# Xadow_-_GSM_Breakout_v1_0.net
KiCad netlist of a schematic drawn in EAGLE
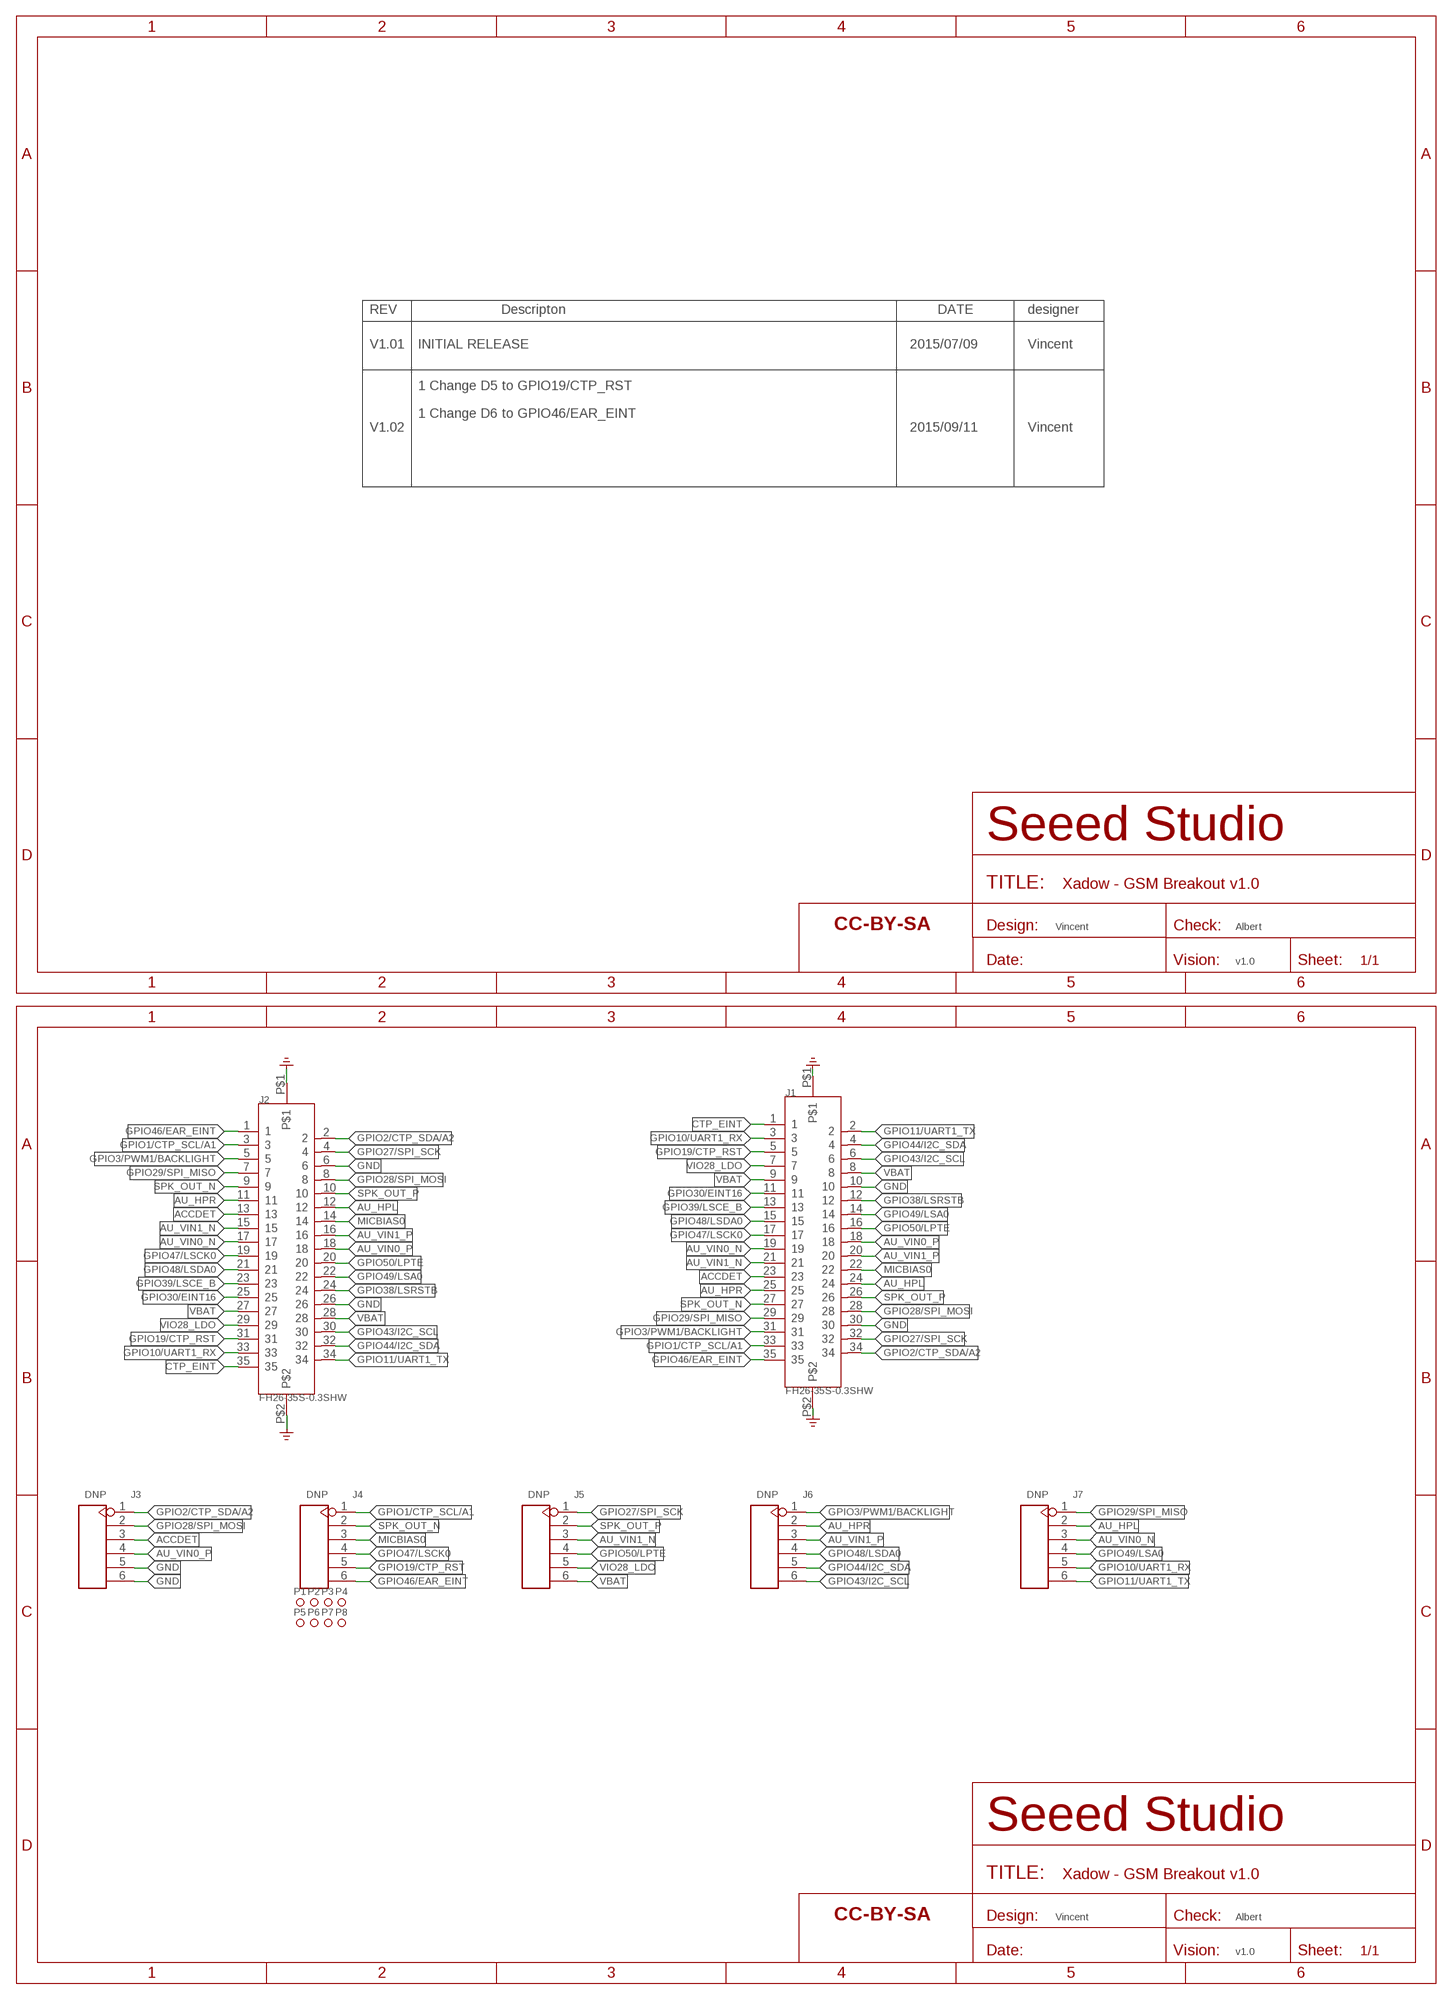
[diagram p0: schematic, sheet 1]

(export (version "E")
  (design (tool "Eeschema 10.0.6"))
  (components
    (comp (ref "FR1")
      (value "SEEEDSTUDIO-OPEN-SCH-FRAME")
      (footprint "eagle-import:SEEEDSTUDIO-PCB-FRAME")
      (libsource (lib "eagle-import") (part "SEEEDSTUDIO-OPEN-SCH-FRAME"))
    )
    (comp (ref "FR2")
      (value "SEEEDSTUDIO-OPEN-SCH-FRAME")
      (footprint "eagle-import:SEEEDSTUDIO-PCB-FRAME")
      (libsource (lib "eagle-import") (part "SEEEDSTUDIO-OPEN-SCH-FRAME"))
    )
    (comp (ref "J1")
      (value "FH26-35S-0.3SHW")
      (footprint "eagle-import:FPC35-SMD-0.3(FH26W)")
      (libsource (lib "eagle-import") (part "FPC-CONNECTER-35P(FH26W-35S-0.3SHW(10))"))
    )
    (comp (ref "J2")
      (value "FH26-35S-0.3SHW")
      (footprint "eagle-import:FPC35-SMD-0.3(FH26W)")
      (libsource (lib "eagle-import") (part "FPC-CONNECTER-35P(FH26W-35S-0.3SHW(10))"))
    )
    (comp (ref "J3")
      (value "DNP")
      (footprint "eagle-import:H6-2.54-C65D35MIL")
      (libsource (lib "eagle-import") (part "HEADER-6P-65/35MIL"))
    )
    (comp (ref "J4")
      (value "DNP")
      (footprint "eagle-import:H6-2.54-C65D35MIL")
      (libsource (lib "eagle-import") (part "HEADER-6P-65/35MIL"))
    )
    (comp (ref "J5")
      (value "DNP")
      (footprint "eagle-import:H6-2.54-C65D35MIL")
      (libsource (lib "eagle-import") (part "HEADER-6P-65/35MIL"))
    )
    (comp (ref "J6")
      (value "DNP")
      (footprint "eagle-import:H6-2.54-C65D35MIL")
      (libsource (lib "eagle-import") (part "HEADER-6P-65/35MIL"))
    )
    (comp (ref "J7")
      (value "DNP")
      (footprint "eagle-import:H6-2.54-C65D35MIL")
      (libsource (lib "eagle-import") (part "HEADER-6P-65/35MIL"))
    )
    (comp (ref "P1")
      (value "MARK-1.0'ANNULAR'")
      (footprint "eagle-import:ROUND-MARK-1.0")
      (fields (field (name "PARTNO") "DNP"))
      (libsource (lib "eagle-import") (part "MARK-1.0'ANNULAR'"))
    )
    (comp (ref "P2")
      (value "MARK-1.0'ANNULAR'")
      (footprint "eagle-import:ROUND-MARK-1.0")
      (fields (field (name "PARTNO") "DNP"))
      (libsource (lib "eagle-import") (part "MARK-1.0'ANNULAR'"))
    )
    (comp (ref "P3")
      (value "MARK-1.0'ANNULAR'")
      (footprint "eagle-import:ROUND-MARK-1.0")
      (fields (field (name "PARTNO") "DNP"))
      (libsource (lib "eagle-import") (part "MARK-1.0'ANNULAR'"))
    )
    (comp (ref "P4")
      (value "MARK-1.0'ANNULAR'")
      (footprint "eagle-import:ROUND-MARK-1.0")
      (fields (field (name "PARTNO") "DNP"))
      (libsource (lib "eagle-import") (part "MARK-1.0'ANNULAR'"))
    )
    (comp (ref "P5")
      (value "MARK-1.0'ANNULAR'")
      (footprint "eagle-import:ROUND-MARK-1.0")
      (fields (field (name "PARTNO") "DNP"))
      (libsource (lib "eagle-import") (part "MARK-1.0'ANNULAR'"))
    )
    (comp (ref "P6")
      (value "MARK-1.0'ANNULAR'")
      (footprint "eagle-import:ROUND-MARK-1.0")
      (fields (field (name "PARTNO") "DNP"))
      (libsource (lib "eagle-import") (part "MARK-1.0'ANNULAR'"))
    )
    (comp (ref "P7")
      (value "MARK-1.0'ANNULAR'")
      (footprint "eagle-import:ROUND-MARK-1.0")
      (fields (field (name "PARTNO") "DNP"))
      (libsource (lib "eagle-import") (part "MARK-1.0'ANNULAR'"))
    )
    (comp (ref "P8")
      (value "MARK-1.0'ANNULAR'")
      (footprint "eagle-import:ROUND-MARK-1.0")
      (fields (field (name "PARTNO") "DNP"))
      (libsource (lib "eagle-import") (part "MARK-1.0'ANNULAR'"))
    )
  )
  (nets
    (net (code "1") (name "ACCDET") (class "Default")
      (node (ref "J1") (pin "23") (pinfunction "23_23") (pintype "bidirectional"))
      (node (ref "J2") (pin "13") (pinfunction "13_13") (pintype "bidirectional"))
      (node (ref "J3") (pin "3") (pinfunction "3_3") (pintype "bidirectional"))
    )
    (net (code "2") (name "AU_HPL") (class "Default")
      (node (ref "J1") (pin "24") (pinfunction "24_24") (pintype "bidirectional"))
      (node (ref "J2") (pin "12") (pinfunction "12_12") (pintype "bidirectional"))
      (node (ref "J7") (pin "2") (pinfunction "2_2") (pintype "bidirectional"))
    )
    (net (code "3") (name "AU_HPR") (class "Default")
      (node (ref "J1") (pin "25") (pinfunction "25_25") (pintype "bidirectional"))
      (node (ref "J2") (pin "11") (pinfunction "11_11") (pintype "bidirectional"))
      (node (ref "J6") (pin "2") (pinfunction "2_2") (pintype "bidirectional"))
    )
    (net (code "4") (name "AU_VIN0_N") (class "Default")
      (node (ref "J1") (pin "19") (pinfunction "19_19") (pintype "bidirectional"))
      (node (ref "J2") (pin "17") (pinfunction "17_17") (pintype "bidirectional"))
      (node (ref "J7") (pin "3") (pinfunction "3_3") (pintype "bidirectional"))
    )
    (net (code "5") (name "AU_VIN0_P") (class "Default")
      (node (ref "J1") (pin "18") (pinfunction "18_18") (pintype "bidirectional"))
      (node (ref "J2") (pin "18") (pinfunction "18_18") (pintype "bidirectional"))
      (node (ref "J3") (pin "4") (pinfunction "4_4") (pintype "bidirectional"))
    )
    (net (code "6") (name "AU_VIN1_N") (class "Default")
      (node (ref "J1") (pin "21") (pinfunction "21_21") (pintype "bidirectional"))
      (node (ref "J2") (pin "15") (pinfunction "15_15") (pintype "bidirectional"))
      (node (ref "J5") (pin "3") (pinfunction "3_3") (pintype "bidirectional"))
    )
    (net (code "7") (name "AU_VIN1_P") (class "Default")
      (node (ref "J1") (pin "20") (pinfunction "20_20") (pintype "bidirectional"))
      (node (ref "J2") (pin "16") (pinfunction "16_16") (pintype "bidirectional"))
      (node (ref "J6") (pin "3") (pinfunction "3_3") (pintype "bidirectional"))
    )
    (net (code "8") (name "CTP_EINT") (class "Default")
      (node (ref "J1") (pin "1") (pinfunction "1_1") (pintype "bidirectional"))
      (node (ref "J2") (pin "35") (pinfunction "35_35") (pintype "bidirectional"))
    )
    (net (code "9") (name "GND") (class "Default")
      (node (ref "J1") (pin "10") (pinfunction "10_10") (pintype "bidirectional"))
      (node (ref "J1") (pin "30") (pinfunction "30_30") (pintype "bidirectional"))
      (node (ref "J1") (pin "P$1") (pinfunction "P$1_P$1") (pintype "bidirectional"))
      (node (ref "J1") (pin "P$2") (pinfunction "P$2_P$2") (pintype "bidirectional"))
      (node (ref "J2") (pin "26") (pinfunction "26_26") (pintype "bidirectional"))
      (node (ref "J2") (pin "6") (pinfunction "6_6") (pintype "bidirectional"))
      (node (ref "J2") (pin "P$1") (pinfunction "P$1_P$1") (pintype "bidirectional"))
      (node (ref "J2") (pin "P$2") (pinfunction "P$2_P$2") (pintype "bidirectional"))
      (node (ref "J3") (pin "5") (pinfunction "5_5") (pintype "bidirectional"))
      (node (ref "J3") (pin "6") (pinfunction "6_6") (pintype "bidirectional"))
    )
    (net (code "10") (name "GPIO1{slash}CTP_SCL{slash}A1") (class "Default")
      (node (ref "J1") (pin "33") (pinfunction "33_33") (pintype "bidirectional"))
      (node (ref "J2") (pin "3") (pinfunction "3_3") (pintype "bidirectional"))
      (node (ref "J4") (pin "1") (pinfunction "1_1") (pintype "bidirectional"))
    )
    (net (code "11") (name "GPIO2{slash}CTP_SDA{slash}A2") (class "Default")
      (node (ref "J1") (pin "34") (pinfunction "34_34") (pintype "bidirectional"))
      (node (ref "J2") (pin "2") (pinfunction "2_2") (pintype "bidirectional"))
      (node (ref "J3") (pin "1") (pinfunction "1_1") (pintype "bidirectional"))
    )
    (net (code "12") (name "GPIO3{slash}PWM1{slash}BACKLIGHT") (class "Default")
      (node (ref "J1") (pin "31") (pinfunction "31_31") (pintype "bidirectional"))
      (node (ref "J2") (pin "5") (pinfunction "5_5") (pintype "bidirectional"))
      (node (ref "J6") (pin "1") (pinfunction "1_1") (pintype "bidirectional"))
    )
    (net (code "13") (name "GPIO10{slash}UART1_RX") (class "Default")
      (node (ref "J1") (pin "3") (pinfunction "3_3") (pintype "bidirectional"))
      (node (ref "J2") (pin "33") (pinfunction "33_33") (pintype "bidirectional"))
      (node (ref "J7") (pin "5") (pinfunction "5_5") (pintype "bidirectional"))
    )
    (net (code "14") (name "GPIO11{slash}UART1_TX") (class "Default")
      (node (ref "J1") (pin "2") (pinfunction "2_2") (pintype "bidirectional"))
      (node (ref "J2") (pin "34") (pinfunction "34_34") (pintype "bidirectional"))
      (node (ref "J7") (pin "6") (pinfunction "6_6") (pintype "bidirectional"))
    )
    (net (code "15") (name "GPIO19{slash}CTP_RST") (class "Default")
      (node (ref "J1") (pin "5") (pinfunction "5_5") (pintype "bidirectional"))
      (node (ref "J2") (pin "31") (pinfunction "31_31") (pintype "bidirectional"))
      (node (ref "J4") (pin "5") (pinfunction "5_5") (pintype "bidirectional"))
    )
    (net (code "16") (name "GPIO27{slash}SPI_SCK") (class "Default")
      (node (ref "J1") (pin "32") (pinfunction "32_32") (pintype "bidirectional"))
      (node (ref "J2") (pin "4") (pinfunction "4_4") (pintype "bidirectional"))
      (node (ref "J5") (pin "1") (pinfunction "1_1") (pintype "bidirectional"))
    )
    (net (code "17") (name "GPIO28{slash}SPI_MOSI") (class "Default")
      (node (ref "J1") (pin "28") (pinfunction "28_28") (pintype "bidirectional"))
      (node (ref "J2") (pin "8") (pinfunction "8_8") (pintype "bidirectional"))
      (node (ref "J3") (pin "2") (pinfunction "2_2") (pintype "bidirectional"))
    )
    (net (code "18") (name "GPIO29{slash}SPI_MISO") (class "Default")
      (node (ref "J1") (pin "29") (pinfunction "29_29") (pintype "bidirectional"))
      (node (ref "J2") (pin "7") (pinfunction "7_7") (pintype "bidirectional"))
      (node (ref "J7") (pin "1") (pinfunction "1_1") (pintype "bidirectional"))
    )
    (net (code "19") (name "GPIO30{slash}EINT16") (class "Default")
      (node (ref "J1") (pin "11") (pinfunction "11_11") (pintype "bidirectional"))
      (node (ref "J2") (pin "25") (pinfunction "25_25") (pintype "bidirectional"))
    )
    (net (code "20") (name "GPIO38{slash}LSRSTB") (class "Default")
      (node (ref "J1") (pin "12") (pinfunction "12_12") (pintype "bidirectional"))
      (node (ref "J2") (pin "24") (pinfunction "24_24") (pintype "bidirectional"))
    )
    (net (code "21") (name "GPIO39{slash}LSCE_B") (class "Default")
      (node (ref "J1") (pin "13") (pinfunction "13_13") (pintype "bidirectional"))
      (node (ref "J2") (pin "23") (pinfunction "23_23") (pintype "bidirectional"))
    )
    (net (code "22") (name "GPIO43{slash}I2C_SCL") (class "Default")
      (node (ref "J1") (pin "6") (pinfunction "6_6") (pintype "bidirectional"))
      (node (ref "J2") (pin "30") (pinfunction "30_30") (pintype "bidirectional"))
      (node (ref "J6") (pin "6") (pinfunction "6_6") (pintype "bidirectional"))
    )
    (net (code "23") (name "GPIO44{slash}I2C_SDA") (class "Default")
      (node (ref "J1") (pin "4") (pinfunction "4_4") (pintype "bidirectional"))
      (node (ref "J2") (pin "32") (pinfunction "32_32") (pintype "bidirectional"))
      (node (ref "J6") (pin "5") (pinfunction "5_5") (pintype "bidirectional"))
    )
    (net (code "24") (name "GPIO46{slash}EAR_EINT") (class "Default")
      (node (ref "J1") (pin "35") (pinfunction "35_35") (pintype "bidirectional"))
      (node (ref "J2") (pin "1") (pinfunction "1_1") (pintype "bidirectional"))
      (node (ref "J4") (pin "6") (pinfunction "6_6") (pintype "bidirectional"))
    )
    (net (code "25") (name "GPIO47{slash}LSCK0") (class "Default")
      (node (ref "J1") (pin "17") (pinfunction "17_17") (pintype "bidirectional"))
      (node (ref "J2") (pin "19") (pinfunction "19_19") (pintype "bidirectional"))
      (node (ref "J4") (pin "4") (pinfunction "4_4") (pintype "bidirectional"))
    )
    (net (code "26") (name "GPIO48{slash}LSDA0") (class "Default")
      (node (ref "J1") (pin "15") (pinfunction "15_15") (pintype "bidirectional"))
      (node (ref "J2") (pin "21") (pinfunction "21_21") (pintype "bidirectional"))
      (node (ref "J6") (pin "4") (pinfunction "4_4") (pintype "bidirectional"))
    )
    (net (code "27") (name "GPIO49{slash}LSA0") (class "Default")
      (node (ref "J1") (pin "14") (pinfunction "14_14") (pintype "bidirectional"))
      (node (ref "J2") (pin "22") (pinfunction "22_22") (pintype "bidirectional"))
      (node (ref "J7") (pin "4") (pinfunction "4_4") (pintype "bidirectional"))
    )
    (net (code "28") (name "GPIO50{slash}LPTE") (class "Default")
      (node (ref "J1") (pin "16") (pinfunction "16_16") (pintype "bidirectional"))
      (node (ref "J2") (pin "20") (pinfunction "20_20") (pintype "bidirectional"))
      (node (ref "J5") (pin "4") (pinfunction "4_4") (pintype "bidirectional"))
    )
    (net (code "29") (name "MICBIAS0") (class "Default")
      (node (ref "J1") (pin "22") (pinfunction "22_22") (pintype "bidirectional"))
      (node (ref "J2") (pin "14") (pinfunction "14_14") (pintype "bidirectional"))
      (node (ref "J4") (pin "3") (pinfunction "3_3") (pintype "bidirectional"))
    )
    (net (code "30") (name "SPK_OUT_N") (class "Default")
      (node (ref "J1") (pin "27") (pinfunction "27_27") (pintype "bidirectional"))
      (node (ref "J2") (pin "9") (pinfunction "9_9") (pintype "bidirectional"))
      (node (ref "J4") (pin "2") (pinfunction "2_2") (pintype "bidirectional"))
    )
    (net (code "31") (name "SPK_OUT_P") (class "Default")
      (node (ref "J1") (pin "26") (pinfunction "26_26") (pintype "bidirectional"))
      (node (ref "J2") (pin "10") (pinfunction "10_10") (pintype "bidirectional"))
      (node (ref "J5") (pin "2") (pinfunction "2_2") (pintype "bidirectional"))
    )
    (net (code "32") (name "VBAT") (class "Default")
      (node (ref "J1") (pin "8") (pinfunction "8_8") (pintype "bidirectional"))
      (node (ref "J1") (pin "9") (pinfunction "9_9") (pintype "bidirectional"))
      (node (ref "J2") (pin "27") (pinfunction "27_27") (pintype "bidirectional"))
      (node (ref "J2") (pin "28") (pinfunction "28_28") (pintype "bidirectional"))
      (node (ref "J5") (pin "6") (pinfunction "6_6") (pintype "bidirectional"))
    )
    (net (code "33") (name "VIO28_LDO") (class "Default")
      (node (ref "J1") (pin "7") (pinfunction "7_7") (pintype "bidirectional"))
      (node (ref "J2") (pin "29") (pinfunction "29_29") (pintype "bidirectional"))
      (node (ref "J5") (pin "5") (pinfunction "5_5") (pintype "bidirectional"))
    )
  )
)
